# BLE.net
KiCad netlist of a schematic drawn in Altium Designer
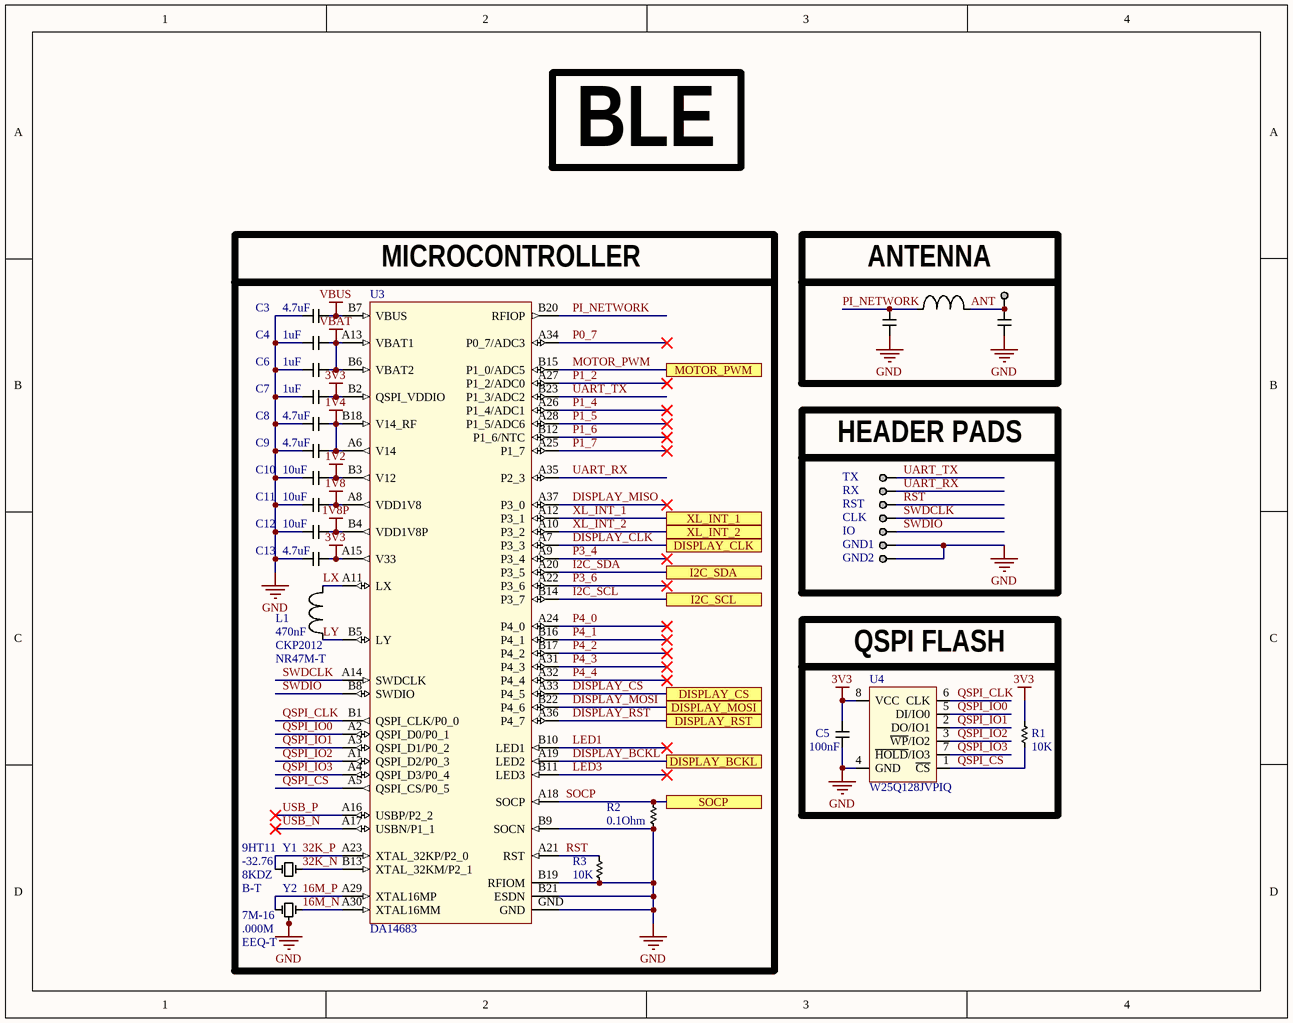
[diagram p0: BLE.SchDoc]

(export (version "E")
  (design (tool "Eeschema 10.0.6"))
  (components
    (comp (ref "ANT1")
      (value "0.1\" Header")
      (footprint "0.1\" Header")
      (libsource (lib "smLib") (part "0.1{dblquote} Header"))
    )
    (comp (ref "C3")
      (value "4.7uF")
      (footprint "CAP_0603_HIGH")
      (description "0603 Capacitor")
      (libsource (lib "smLib") (part "Capacitor_0603"))
    )
    (comp (ref "C4")
      (value "1uF")
      (footprint "CAP_0603_HIGH")
      (description "0603 Capacitor")
      (libsource (lib "smLib") (part "Capacitor_0603"))
    )
    (comp (ref "C5")
      (value "100nF")
      (footprint "CAP_0603_HIGH")
      (description "0603 Capacitor")
      (libsource (lib "smLib") (part "Capacitor_0603"))
    )
    (comp (ref "C6")
      (value "1uF")
      (footprint "CAP_0603_HIGH")
      (description "0603 Capacitor")
      (libsource (lib "smLib") (part "Capacitor_0603"))
    )
    (comp (ref "C7")
      (value "1uF")
      (footprint "CAP_0603_HIGH")
      (description "0603 Capacitor")
      (libsource (lib "smLib") (part "Capacitor_0603"))
    )
    (comp (ref "C8")
      (value "4.7uF")
      (footprint "CAP_0603_HIGH")
      (description "0603 Capacitor")
      (libsource (lib "smLib") (part "Capacitor_0603"))
    )
    (comp (ref "C9")
      (value "4.7uF")
      (footprint "CAP_0603_HIGH")
      (description "0603 Capacitor")
      (libsource (lib "smLib") (part "Capacitor_0603"))
    )
    (comp (ref "C10")
      (value "10uF")
      (footprint "CAP_0603_HIGH")
      (description "0603 Capacitor")
      (libsource (lib "smLib") (part "Capacitor_0603"))
    )
    (comp (ref "C11")
      (value "10uF")
      (footprint "CAP_0603_HIGH")
      (description "0603 Capacitor")
      (libsource (lib "smLib") (part "Capacitor_0603"))
    )
    (comp (ref "C12")
      (value "10uF")
      (footprint "CAP_0603_HIGH")
      (description "0603 Capacitor")
      (libsource (lib "smLib") (part "Capacitor_0603"))
    )
    (comp (ref "C13")
      (value "4.7uF")
      (footprint "CAP_0603_HIGH")
      (description "0603 Capacitor")
      (libsource (lib "smLib") (part "Capacitor_0603"))
    )
    (comp (ref "C16")
      (value "C")
      (footprint "CAP_0402_MEDIUM")
      (description "0402 Capacitor")
      (libsource (lib "smLib") (part "Capacitor_0402"))
    )
    (comp (ref "C17")
      (value "C")
      (footprint "CAP_0402_MEDIUM")
      (description "0402 Capacitor")
      (libsource (lib "smLib") (part "Capacitor_0402"))
    )
    (comp (ref "CLK")
      (value "0.1\" Pad")
      (footprint "0.1\" Pad")
      (libsource (lib "smLib") (part "0.1{dblquote} Pad"))
    )
    (comp (ref "GND1")
      (value "0.1\" Pad")
      (footprint "0.1\" Pad")
      (libsource (lib "smLib") (part "0.1{dblquote} Pad"))
    )
    (comp (ref "GND2")
      (value "0.1\" Pad")
      (footprint "0.1\" Pad")
      (libsource (lib "smLib") (part "0.1{dblquote} Pad"))
    )
    (comp (ref "IO")
      (value "0.1\" Pad")
      (footprint "0.1\" Pad")
      (libsource (lib "smLib") (part "0.1{dblquote} Pad"))
    )
    (comp (ref "L1")
      (value "470nF")
      (footprint "IND_0805_HIGH")
      (description "Inductor_0805")
      (fields
        (field (name "PARAMETER 1") "CKP2012")
        (field (name "PARAMETER 2") "NR47M-T")
        (field (name "Comment") "CKP2012NR47M-T")
      )
      (libsource (lib "smLib") (part "Inductor_0805"))
    )
    (comp (ref "L2")
      (value "L")
      (footprint "IND_0402_MEDIUM")
      (description "Inductor_0402")
      (libsource (lib "smLib") (part "Inductor_0402"))
    )
    (comp (ref "R1")
      (value "10K")
      (footprint "RES_0603_HIGH")
      (description "0603 Resistor")
      (libsource (lib "smLib") (part "Resistor_0603"))
    )
    (comp (ref "R2")
      (value "0.1Ohm")
      (footprint "RES_0603_HIGH")
      (description "0603 Resistor")
      (libsource (lib "smLib") (part "Resistor_0603"))
    )
    (comp (ref "R3")
      (value "10K")
      (footprint "RES_0603_HIGH")
      (description "0603 Resistor")
      (libsource (lib "smLib") (part "Resistor_0603"))
    )
    (comp (ref "RST")
      (value "0.1\" Pad")
      (footprint "0.1\" Pad")
      (libsource (lib "smLib") (part "0.1{dblquote} Pad"))
    )
    (comp (ref "RX")
      (value "0.1\" Pad")
      (footprint "0.1\" Pad")
      (libsource (lib "smLib") (part "0.1{dblquote} Pad"))
    )
    (comp (ref "TX")
      (value "0.1\" Pad")
      (footprint "0.1\" Pad")
      (libsource (lib "smLib") (part "0.1{dblquote} Pad"))
    )
    (comp (ref "U3")
      (value "DA14683")
      (footprint "DA14683")
      (description "SmartBond DA14683 Single-chip high-security Bluetooth 5 solution with expandable memory")
      (libsource (lib "smLib") (part "DA14683"))
    )
    (comp (ref "U4")
      (value "W25Q128JVPIQ")
      (footprint "W25Q128JVPIQ")
      (description "FLASH - NOR Memory IC 128Mb (16M x 8) SPI - Quad I/O, QPI, DTR 133MHz  8-WSON (6x5)")
      (libsource (lib "smLib") (part "W25Q128JVPIQ"))
    )
    (comp (ref "Y1")
      (value "9HT11-32.768KDZB-T")
      (footprint "9HT11-32.768KDZB-T")
      (description "32.768kHz ±20ppm Crystal 6pF 90 kOhms 2-SMD, No Lead")
      (fields
        (field (name "PARAMETER 1") "9HT11")
        (field (name "PARAMETER 2") "-32.76")
        (field (name "PARAMETER 3") "8KDZ")
        (field (name "PARAMETER 4") "B-T")
      )
      (libsource (lib "smLib") (part "9HT11-32.768KDZB-T"))
    )
    (comp (ref "Y2")
      (value "7M-16.000MEEQ-T")
      (footprint "7M-16.000MEEQ-T")
      (description "16MHz ±10ppm Crystal 10pF 80 Ohms 4-SMD, No Lead")
      (fields
        (field (name "PARAMETER 1") "7M-16")
        (field (name "PARAMETER 2") ".000M")
        (field (name "PARAMETER 3") "EEQ-T")
      )
      (libsource (lib "smLib") (part "7M-16.000MEEQ-T"))
    )
  )
  (nets
    (net (code "1") (name "/16M_N") (class "Default")
      (node (ref "U3") (pin "A30") (pinfunction "XTAL16MM_A30") (pintype "input"))
      (node (ref "Y2") (pin "3") (pinfunction "3_3") (pintype "passive"))
    )
    (net (code "2") (name "/16M_P") (class "Default")
      (node (ref "U3") (pin "A29") (pinfunction "XTAL16MP_A29") (pintype "input"))
      (node (ref "Y2") (pin "1") (pinfunction "1_1") (pintype "passive"))
    )
    (net (code "3") (name "/32K_N") (class "Default")
      (node (ref "U3") (pin "B13") (pinfunction "XTAL_32KM/P2_1_B13") (pintype "input"))
      (node (ref "Y1") (pin "2") (pinfunction "2_2") (pintype "passive"))
    )
    (net (code "4") (name "/32K_P") (class "Default")
      (node (ref "U3") (pin "A23") (pinfunction "XTAL_32KP/P2_0_A23") (pintype "input"))
      (node (ref "Y1") (pin "1") (pinfunction "1_1") (pintype "passive"))
    )
    (net (code "5") (name "/ANT") (class "Default")
      (node (ref "ANT1") (pin "1") (pinfunction "1_1") (pintype "passive"))
      (node (ref "C17") (pin "2") (pinfunction "2_2") (pintype "passive"))
      (node (ref "L2") (pin "1") (pinfunction "1_1") (pintype "passive"))
    )
    (net (code "6") (name "/DISPLAY_BCKL") (class "Default")
      (node (ref "U3") (pin "A19") (pinfunction "LED2_A19") (pintype "input"))
    )
    (net (code "7") (name "/DISPLAY_CLK") (class "Default")
      (node (ref "U3") (pin "A7") (pinfunction "P3_3_A7") (pintype "bidirectional"))
    )
    (net (code "8") (name "/DISPLAY_CS") (class "Default")
      (node (ref "U3") (pin "A33") (pinfunction "P4_5_A33") (pintype "bidirectional"))
    )
    (net (code "9") (name "/DISPLAY_MISO") (class "Default")
      (node (ref "U3") (pin "A37") (pinfunction "P3_0_A37") (pintype "bidirectional+no_connect"))
    )
    (net (code "10") (name "/DISPLAY_MOSI") (class "Default")
      (node (ref "U3") (pin "B22") (pinfunction "P4_6_B22") (pintype "bidirectional"))
    )
    (net (code "11") (name "/DISPLAY_RST") (class "Default")
      (node (ref "U3") (pin "A36") (pinfunction "P4_7_A36") (pintype "bidirectional"))
    )
    (net (code "12") (name "/I2C_SCL") (class "Default")
      (node (ref "U3") (pin "B14") (pinfunction "P3_7_B14") (pintype "bidirectional"))
    )
    (net (code "13") (name "/I2C_SDA") (class "Default")
      (node (ref "U3") (pin "A20") (pinfunction "P3_5_A20") (pintype "bidirectional"))
    )
    (net (code "14") (name "/LED1") (class "Default")
      (node (ref "U3") (pin "B10") (pinfunction "LED1_B10") (pintype "input+no_connect"))
    )
    (net (code "15") (name "/LED3") (class "Default")
      (node (ref "U3") (pin "B11") (pinfunction "LED3_B11") (pintype "input+no_connect"))
    )
    (net (code "16") (name "/LX") (class "Default")
      (node (ref "L1") (pin "2") (pinfunction "2_2") (pintype "passive"))
      (node (ref "U3") (pin "A11") (pinfunction "LX_A11") (pintype "bidirectional"))
    )
    (net (code "17") (name "/LY") (class "Default")
      (node (ref "L1") (pin "1") (pinfunction "1_1") (pintype "passive"))
      (node (ref "U3") (pin "B5") (pinfunction "LY_B5") (pintype "bidirectional"))
    )
    (net (code "18") (name "/MOTOR_PWM") (class "Default")
      (node (ref "U3") (pin "B15") (pinfunction "P1_0/ADC5_B15") (pintype "bidirectional"))
    )
    (net (code "19") (name "/P0_7") (class "Default")
      (node (ref "U3") (pin "A34") (pinfunction "P0_7/ADC3_A34") (pintype "bidirectional+no_connect"))
    )
    (net (code "20") (name "/P1_2") (class "Default")
      (node (ref "U3") (pin "A27") (pinfunction "P1_2/ADC0_A27") (pintype "bidirectional+no_connect"))
    )
    (net (code "21") (name "/P1_4") (class "Default")
      (node (ref "U3") (pin "A26") (pinfunction "P1_4/ADC1_A26") (pintype "bidirectional+no_connect"))
    )
    (net (code "22") (name "/P1_5") (class "Default")
      (node (ref "U3") (pin "A28") (pinfunction "P1_5/ADC6_A28") (pintype "bidirectional+no_connect"))
    )
    (net (code "23") (name "/P1_6") (class "Default")
      (node (ref "U3") (pin "B12") (pinfunction "P1_6/NTC_B12") (pintype "bidirectional+no_connect"))
    )
    (net (code "24") (name "/P1_7") (class "Default")
      (node (ref "U3") (pin "A25") (pinfunction "P1_7_A25") (pintype "bidirectional+no_connect"))
    )
    (net (code "25") (name "/P3_4") (class "Default")
      (node (ref "U3") (pin "A9") (pinfunction "P3_4_A9") (pintype "bidirectional+no_connect"))
    )
    (net (code "26") (name "/P3_6") (class "Default")
      (node (ref "U3") (pin "A22") (pinfunction "P3_6_A22") (pintype "bidirectional+no_connect"))
    )
    (net (code "27") (name "/P4_0") (class "Default")
      (node (ref "U3") (pin "A24") (pinfunction "P4_0_A24") (pintype "bidirectional+no_connect"))
    )
    (net (code "28") (name "/P4_1") (class "Default")
      (node (ref "U3") (pin "B16") (pinfunction "P4_1_B16") (pintype "bidirectional+no_connect"))
    )
    (net (code "29") (name "/P4_2") (class "Default")
      (node (ref "U3") (pin "B17") (pinfunction "P4_2_B17") (pintype "bidirectional+no_connect"))
    )
    (net (code "30") (name "/P4_3") (class "Default")
      (node (ref "U3") (pin "A31") (pinfunction "P4_3_A31") (pintype "bidirectional+no_connect"))
    )
    (net (code "31") (name "/P4_4") (class "Default")
      (node (ref "U3") (pin "A32") (pinfunction "P4_4_A32") (pintype "bidirectional+no_connect"))
    )
    (net (code "32") (name "/PI_NETWORK") (class "Default")
      (node (ref "C16") (pin "2") (pinfunction "2_2") (pintype "passive"))
      (node (ref "L2") (pin "2") (pinfunction "2_2") (pintype "passive"))
      (node (ref "U3") (pin "B20") (pinfunction "RFIOP_B20") (pintype "output"))
    )
    (net (code "33") (name "/QSPI_CLK") (class "Default")
      (node (ref "U3") (pin "B1") (pinfunction "QSPI_CLK/P0_0_B1") (pintype "output"))
      (node (ref "U4") (pin "6") (pinfunction "CLK_6") (pintype "passive"))
    )
    (net (code "34") (name "/QSPI_CS") (class "Default")
      (node (ref "R1") (pin "1") (pinfunction "1_1") (pintype "passive"))
      (node (ref "U3") (pin "A5") (pinfunction "QSPI_CS/P0_5_A5") (pintype "output"))
      (node (ref "U4") (pin "1") (pinfunction "~{CS}_1") (pintype "passive"))
    )
    (net (code "35") (name "/QSPI_IO0") (class "Default")
      (node (ref "U3") (pin "A2") (pinfunction "QSPI_D0/P0_1_A2") (pintype "bidirectional"))
      (node (ref "U4") (pin "5") (pinfunction "DI/IO0_5") (pintype "passive"))
    )
    (net (code "36") (name "/QSPI_IO1") (class "Default")
      (node (ref "U3") (pin "A3") (pinfunction "QSPI_D1/P0_2_A3") (pintype "bidirectional"))
      (node (ref "U4") (pin "2") (pinfunction "DO/IO1_2") (pintype "passive"))
    )
    (net (code "37") (name "/QSPI_IO2") (class "Default")
      (node (ref "U3") (pin "A1") (pinfunction "QSPI_D2/P0_3_A1") (pintype "bidirectional"))
      (node (ref "U4") (pin "3") (pinfunction "~{WP}/IO2_3") (pintype "passive"))
    )
    (net (code "38") (name "/QSPI_IO3") (class "Default")
      (node (ref "U3") (pin "A4") (pinfunction "QSPI_D3/P0_4_A4") (pintype "bidirectional"))
      (node (ref "U4") (pin "7") (pinfunction "~{HOLD}/IO3_7") (pintype "passive"))
    )
    (net (code "39") (name "/RST") (class "Default")
      (node (ref "R3") (pin "2") (pinfunction "2_2") (pintype "passive"))
      (node (ref "RST") (pin "1") (pinfunction "1_1") (pintype "passive"))
      (node (ref "U3") (pin "A21") (pinfunction "RST_A21") (pintype "input"))
    )
    (net (code "40") (name "/SOCP") (class "Default")
      (node (ref "R2") (pin "2") (pinfunction "2_2") (pintype "passive"))
      (node (ref "U3") (pin "A18") (pinfunction "SOCP_A18") (pintype "input"))
    )
    (net (code "41") (name "/SWDCLK") (class "Default")
      (node (ref "CLK") (pin "1") (pinfunction "1_1") (pintype "passive"))
      (node (ref "U3") (pin "A14") (pinfunction "SWDCLK_A14") (pintype "input"))
    )
    (net (code "42") (name "/SWDIO") (class "Default")
      (node (ref "IO") (pin "1") (pinfunction "1_1") (pintype "passive"))
      (node (ref "U3") (pin "B8") (pinfunction "SWDIO_B8") (pintype "bidirectional"))
    )
    (net (code "43") (name "/UART_RX") (class "Default")
      (node (ref "RX") (pin "1") (pinfunction "1_1") (pintype "passive"))
      (node (ref "U3") (pin "A35") (pinfunction "P2_3_A35") (pintype "bidirectional"))
    )
    (net (code "44") (name "/UART_TX") (class "Default")
      (node (ref "TX") (pin "1") (pinfunction "1_1") (pintype "passive"))
      (node (ref "U3") (pin "B23") (pinfunction "P1_3/ADC2_B23") (pintype "bidirectional"))
    )
    (net (code "45") (name "/USB_N") (class "Default")
      (node (ref "U3") (pin "A17") (pinfunction "USBN/P1_1_A17") (pintype "bidirectional+no_connect"))
    )
    (net (code "46") (name "/USB_P") (class "Default")
      (node (ref "U3") (pin "A16") (pinfunction "USBP/P2_2_A16") (pintype "bidirectional+no_connect"))
    )
    (net (code "47") (name "/XL_INT_1") (class "Default")
      (node (ref "U3") (pin "A12") (pinfunction "P3_1_A12") (pintype "bidirectional"))
    )
    (net (code "48") (name "/XL_INT_2") (class "Default")
      (node (ref "U3") (pin "A10") (pinfunction "P3_2_A10") (pintype "bidirectional"))
    )
    (net (code "49") (name "1V2") (class "Default")
      (node (ref "C10") (pin "1") (pinfunction "1_1") (pintype "passive"))
      (node (ref "U3") (pin "B3") (pinfunction "V12_B3") (pintype "output"))
    )
    (net (code "50") (name "1V4") (class "Default")
      (node (ref "C8") (pin "1") (pinfunction "1_1") (pintype "passive"))
      (node (ref "C9") (pin "1") (pinfunction "1_1") (pintype "passive"))
      (node (ref "U3") (pin "A6") (pinfunction "V14_A6") (pintype "output"))
      (node (ref "U3") (pin "B18") (pinfunction "V14_RF_B18") (pintype "input"))
    )
    (net (code "51") (name "1V8") (class "Default")
      (node (ref "C11") (pin "1") (pinfunction "1_1") (pintype "passive"))
      (node (ref "U3") (pin "A8") (pinfunction "VDD1V8_A8") (pintype "output"))
    )
    (net (code "52") (name "1V8P") (class "Default")
      (node (ref "C12") (pin "1") (pinfunction "1_1") (pintype "passive"))
      (node (ref "U3") (pin "B4") (pinfunction "VDD1V8P_B4") (pintype "output"))
    )
    (net (code "53") (name "3V3") (class "Default")
      (node (ref "C13") (pin "1") (pinfunction "1_1") (pintype "passive"))
      (node (ref "C5") (pin "1") (pinfunction "1_1") (pintype "passive"))
      (node (ref "C7") (pin "1") (pinfunction "1_1") (pintype "passive"))
      (node (ref "R1") (pin "2") (pinfunction "2_2") (pintype "passive"))
      (node (ref "U3") (pin "A15") (pinfunction "V33_A15") (pintype "output"))
      (node (ref "U3") (pin "B2") (pinfunction "QSPI_VDDIO_B2") (pintype "input"))
      (node (ref "U4") (pin "8") (pinfunction "VCC_8") (pintype "passive"))
    )
    (net (code "54") (name "GND") (class "Default")
      (node (ref "C10") (pin "2") (pinfunction "2_2") (pintype "passive"))
      (node (ref "C11") (pin "2") (pinfunction "2_2") (pintype "passive"))
      (node (ref "C12") (pin "2") (pinfunction "2_2") (pintype "passive"))
      (node (ref "C13") (pin "2") (pinfunction "2_2") (pintype "passive"))
      (node (ref "C16") (pin "1") (pinfunction "1_1") (pintype "passive"))
      (node (ref "C17") (pin "1") (pinfunction "1_1") (pintype "passive"))
      (node (ref "C3") (pin "2") (pinfunction "2_2") (pintype "passive"))
      (node (ref "C4") (pin "2") (pinfunction "2_2") (pintype "passive"))
      (node (ref "C5") (pin "2") (pinfunction "2_2") (pintype "passive"))
      (node (ref "C6") (pin "2") (pinfunction "2_2") (pintype "passive"))
      (node (ref "C7") (pin "2") (pinfunction "2_2") (pintype "passive"))
      (node (ref "C8") (pin "2") (pinfunction "2_2") (pintype "passive"))
      (node (ref "C9") (pin "2") (pinfunction "2_2") (pintype "passive"))
      (node (ref "GND1") (pin "1") (pinfunction "1_1") (pintype "passive"))
      (node (ref "GND2") (pin "1") (pinfunction "1_1") (pintype "passive"))
      (node (ref "R2") (pin "1") (pinfunction "1_1") (pintype "passive"))
      (node (ref "R3") (pin "1") (pinfunction "1_1") (pintype "passive"))
      (node (ref "U3") (pin "B19") (pinfunction "RFIOM_B19") (pintype "power_in"))
      (node (ref "U3") (pin "B21") (pinfunction "ESDN_B21") (pintype "power_in"))
      (node (ref "U3") (pin "B9") (pinfunction "SOCN_B9") (pintype "input"))
      (node (ref "U3") (pin "GND") (pinfunction "GND_GND") (pintype "power_in"))
      (node (ref "U4") (pin "4") (pinfunction "GND_4") (pintype "passive"))
      (node (ref "Y2") (pin "2") (pinfunction "2_2") (pintype "passive"))
      (node (ref "Y2") (pin "4") (pinfunction "4_4") (pintype "passive"))
    )
    (net (code "55") (name "VBAT") (class "Default")
      (node (ref "C4") (pin "1") (pinfunction "1_1") (pintype "passive"))
      (node (ref "C6") (pin "1") (pinfunction "1_1") (pintype "passive"))
      (node (ref "U3") (pin "A13") (pinfunction "VBAT1_A13") (pintype "input"))
      (node (ref "U3") (pin "B6") (pinfunction "VBAT2_B6") (pintype "input"))
    )
    (net (code "56") (name "VBUS") (class "Default")
      (node (ref "C3") (pin "1") (pinfunction "1_1") (pintype "passive"))
      (node (ref "U3") (pin "B7") (pinfunction "VBUS_B7") (pintype "input"))
    )
  )
)
